# Fri3D_2026_Peripherals.net
KiCad netlist of a schematic drawn in Altium Designer
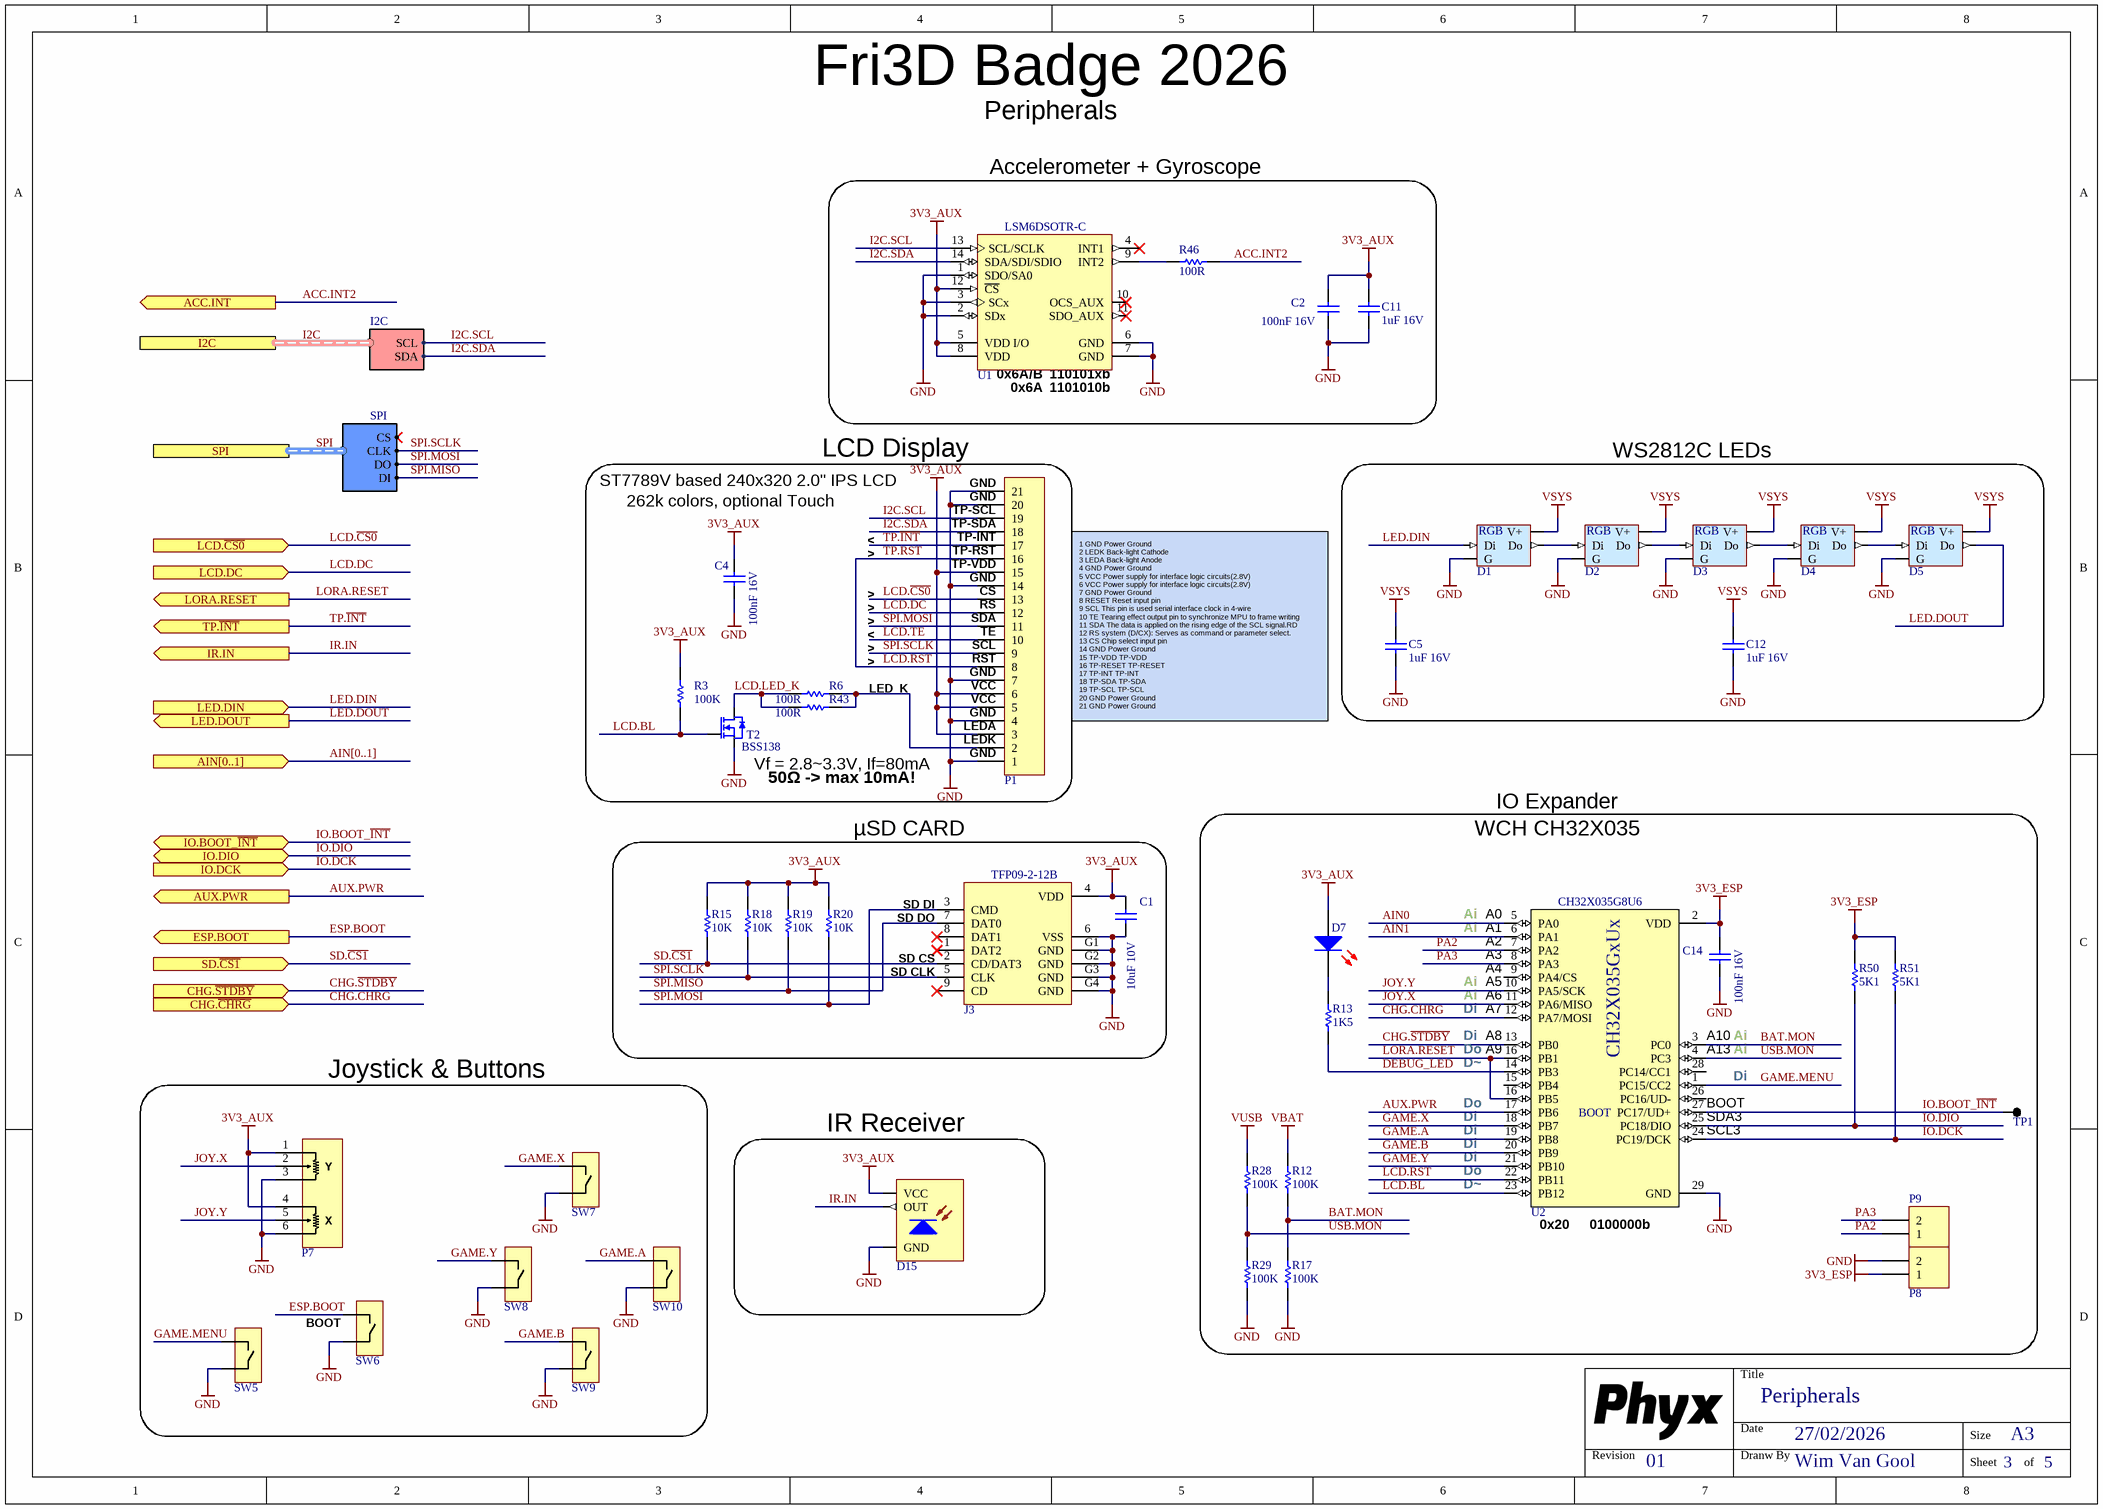
[diagram p0: Fri3D_2026_Peripherals.SchDoc]

(export (version "E")
  (design (tool "Eeschema 10.0.6"))
  (components
    (comp (ref "C1")
      (value "10uF 10V")
      (footprint "C0805_N")
      (description "Capacitor Ceramic")
      (libsource (lib "Phyx_Components") (part "CAP_CERAMIC"))
    )
    (comp (ref "C2")
      (value "100nF 16V")
      (footprint "C0603_N")
      (description "Capacitor Ceramic")
      (libsource (lib "Phyx_Components") (part "CAP_CERAMIC"))
    )
    (comp (ref "C4")
      (value "100nF 16V")
      (footprint "C0603_N")
      (description "Capacitor Ceramic")
      (libsource (lib "Phyx_Components") (part "CAP_CERAMIC"))
    )
    (comp (ref "C5")
      (value "1uF 16V")
      (footprint "C0603_N")
      (description "Capacitor Ceramic")
      (libsource (lib "Phyx_Components") (part "CAP_CERAMIC"))
    )
    (comp (ref "C11")
      (value "1uF 16V")
      (footprint "C0603_N")
      (description "Capacitor Ceramic")
      (libsource (lib "Phyx_Components") (part "CAP_CERAMIC"))
    )
    (comp (ref "C12")
      (value "1uF 16V")
      (footprint "C0603_N")
      (description "Capacitor Ceramic")
      (libsource (lib "Phyx_Components") (part "CAP_CERAMIC"))
    )
    (comp (ref "C14")
      (value "100nF 16V")
      (footprint "C0603_N")
      (description "Capacitor Ceramic")
      (libsource (lib "Phyx_Components") (part "CAP_CERAMIC"))
    )
    (comp (ref "D1")
      (value "WS2812 based digital RGB LED 5050 White package reduced current")
      (footprint "LED_5050_WS2812B_WHITE")
      (description "=Description")
      (libsource (lib "Phyx_Components") (part "LED_RGB_WS2812B_5050"))
    )
    (comp (ref "D2")
      (value "WS2812 based digital RGB LED 5050 White package reduced current")
      (footprint "LED_5050_WS2812B_WHITE")
      (description "=Description")
      (libsource (lib "Phyx_Components") (part "LED_RGB_WS2812B_5050"))
    )
    (comp (ref "D3")
      (value "WS2812 based digital RGB LED 5050 White package reduced current")
      (footprint "LED_5050_WS2812B_WHITE")
      (description "=Description")
      (libsource (lib "Phyx_Components") (part "LED_RGB_WS2812B_5050"))
    )
    (comp (ref "D4")
      (value "WS2812 based digital RGB LED 5050 White package reduced current")
      (footprint "LED_5050_WS2812B_WHITE")
      (description "=Description")
      (libsource (lib "Phyx_Components") (part "LED_RGB_WS2812B_5050"))
    )
    (comp (ref "D5")
      (value "WS2812 based digital RGB LED 5050 White package reduced current")
      (footprint "LED_5050_WS2812B_WHITE")
      (description "=Description")
      (libsource (lib "Phyx_Components") (part "LED_RGB_WS2812B_5050"))
    )
    (comp (ref "D7")
      (value "Default 0805 Red LED")
      (footprint "LED_0805_RD")
      (description "=Description")
      (libsource (lib "Phyx_Components") (part "LED_RED"))
    )
    (comp (ref "D15")
      (value "ZIRM-5042B-42-Z2 Infrared Receiver 38 kHz 45° 2.7-5.5V 940nm")
      (footprint "CHAU_ZIRM-5042B-42-Z2")
      (description "=Description")
      (libsource (lib "Phyx_Components") (part "PHO_IR_TSOP381x"))
    )
    (comp (ref "J3")
      (value "Micro SD PiPo Push-Push")
      (footprint "TFP09-2-12B")
      (description "=Description")
      (fields (field (name "SUPPLIER PART NUMBER 1") "TFP09-2-12B"))
      (libsource (lib "Phyx_Components") (part "TFP09-2-12B"))
    )
    (comp (ref "P1")
      (value "FH35C-21S-0.3SHW Top and Bottom Contacts 0.3mm 21pin")
      (footprint "HRS_FH35C-21S-0.3SHW")
      (libsource (lib "Phyx_Components") (part "Header 21"))
    )
    (comp (ref "P7")
      (value "PSP Mini Joystick")
      (footprint "PSP_Mini_Joystick")
      (libsource (lib "Phyx_Components") (part "PSP_Mini_Joystick"))
    )
    (comp (ref "P8")
      (value "Header 2")
      (footprint "HDR1X2")
      (libsource (lib "Phyx_Components") (part "Header 2"))
    )
    (comp (ref "P9")
      (value "Header 2")
      (footprint "HDR1X2")
      (libsource (lib "Phyx_Components") (part "Header 2"))
    )
    (comp (ref "R3")
      (value "100K")
      (footprint "R0603_N")
      (libsource (lib "Phyx_Components") (part "RESISTOR"))
    )
    (comp (ref "R6")
      (value "100R")
      (footprint "R0603_N")
      (libsource (lib "Phyx_Components") (part "RESISTOR"))
    )
    (comp (ref "R12")
      (value "100K")
      (footprint "R0603_N")
      (libsource (lib "Phyx_Components") (part "RESISTOR"))
    )
    (comp (ref "R13")
      (value "1K5")
      (footprint "R0603_N")
      (libsource (lib "Phyx_Components") (part "RESISTOR"))
    )
    (comp (ref "R15")
      (value "10K")
      (footprint "R0603_N")
      (libsource (lib "Phyx_Components") (part "RESISTOR"))
    )
    (comp (ref "R17")
      (value "100K")
      (footprint "R0603_N")
      (libsource (lib "Phyx_Components") (part "RESISTOR"))
    )
    (comp (ref "R18")
      (value "10K")
      (footprint "R0603_N")
      (libsource (lib "Phyx_Components") (part "RESISTOR"))
    )
    (comp (ref "R19")
      (value "10K")
      (footprint "R0603_N")
      (libsource (lib "Phyx_Components") (part "RESISTOR"))
    )
    (comp (ref "R20")
      (value "10K")
      (footprint "R0603_N")
      (libsource (lib "Phyx_Components") (part "RESISTOR"))
    )
    (comp (ref "R28")
      (value "100K")
      (footprint "R0603_N")
      (libsource (lib "Phyx_Components") (part "RESISTOR"))
    )
    (comp (ref "R29")
      (value "100K")
      (footprint "R0603_N")
      (libsource (lib "Phyx_Components") (part "RESISTOR"))
    )
    (comp (ref "R43")
      (value "100R")
      (footprint "R0603_N")
      (libsource (lib "Phyx_Components") (part "RESISTOR"))
    )
    (comp (ref "R46")
      (value "100R")
      (footprint "R0603_N")
      (libsource (lib "Phyx_Components") (part "RESISTOR"))
    )
    (comp (ref "R50")
      (value "5K1")
      (footprint "R0603_N")
      (libsource (lib "Phyx_Components") (part "RESISTOR"))
    )
    (comp (ref "R51")
      (value "5K1")
      (footprint "R0603_N")
      (libsource (lib "Phyx_Components") (part "RESISTOR"))
    )
    (comp (ref "SW5")
      (value "SKPMAME010 6x6 TACTG Switch")
      (footprint "ALPS_SKPMAME010")
      (libsource (lib "Phyx_Components") (part "SW_TACT"))
    )
    (comp (ref "SW6")
      (value "SKPMAME010 6x6 TACTG Switch")
      (footprint "ALPS_SKPMAME010")
      (libsource (lib "Phyx_Components") (part "SW_TACT"))
    )
    (comp (ref "SW7")
      (value "SKPMAME010 6x6 TACTG Switch")
      (footprint "ALPS_SKPMAME010")
      (libsource (lib "Phyx_Components") (part "SW_TACT"))
    )
    (comp (ref "SW8")
      (value "SKPMAME010 6x6 TACTG Switch")
      (footprint "ALPS_SKPMAME010")
      (libsource (lib "Phyx_Components") (part "SW_TACT"))
    )
    (comp (ref "SW9")
      (value "SKPMAME010 6x6 TACTG Switch")
      (footprint "ALPS_SKPMAME010")
      (libsource (lib "Phyx_Components") (part "SW_TACT"))
    )
    (comp (ref "SW10")
      (value "SKPMAME010 6x6 TACTG Switch")
      (footprint "ALPS_SKPMAME010")
      (libsource (lib "Phyx_Components") (part "SW_TACT"))
    )
    (comp (ref "T2")
      (value "BSS138")
      (footprint "SOT23-3")
      (fields (field (name "Comment") "0.2A N-Ch MOSFET Vgs 3.2"))
      (libsource (lib "Phyx_Components") (part "N_MOSFET_GSD"))
    )
    (comp (ref "TP1")
      (value "TEST_PAD")
      (footprint "TP_1.5mm_0.9mm")
      (libsource (lib "Phyx_Components") (part "TEST_PAD"))
    )
    (comp (ref "U1")
      (value "LSM6DSOTR-C")
      (footprint "STM_LGA14_2.5x3")
      (description "=Description")
      (fields (field (name "Comment") "Acceleration ±2, ±4, ±8, ±16g Gyro ±125, ±250, ±500, ±1000, ±2000dps"))
      (libsource (lib "Phyx_Components") (part "STM_LSM6DSO"))
    )
    (comp (ref "U2")
      (value "CH32X035G8U6")
      (footprint "QFN_28_4.0x4.0_P0.4")
      (fields
        (field (name "Comment") "WCH CH32X035G8U6 QFN28 RISC-V 32-bit MCU, 62KB Flash, 10KB RAM, USB PD")
      )
      (libsource (lib "Phyx_Components") (part "WCH_CH32X035GxUx"))
    )
  )
  (nets
    (net (code "3") (name "/ACC.INT2") (class "Default")
      (node (ref "R46") (pin "2") (pinfunction "2_2") (pintype "passive"))
    )
    (net (code "4") (name "/AIN0") (class "Default")
      (node (ref "U2") (pin "5") (pinfunction "PA0_5") (pintype "bidirectional"))
    )
    (net (code "5") (name "/AIN1") (class "Default")
      (node (ref "U2") (pin "6") (pinfunction "PA1_6") (pintype "bidirectional"))
    )
    (net (code "7") (name "/AUX.PWR") (class "Default")
      (node (ref "U2") (pin "17") (pinfunction "PB6_17") (pintype "bidirectional"))
    )
    (net (code "8") (name "/BAT.MON") (class "Default")
      (node (ref "R12") (pin "2") (pinfunction "2_2") (pintype "passive"))
      (node (ref "R17") (pin "1") (pinfunction "1_1") (pintype "passive"))
      (node (ref "U2") (pin "3") (pinfunction "PC0_3") (pintype "bidirectional"))
    )
    (net (code "9") (name "/CHG.~{CHRG}") (class "Default")
      (node (ref "U2") (pin "12") (pinfunction "PA7/MOSI_12") (pintype "bidirectional"))
    )
    (net (code "10") (name "/CHG.~{STDBY}") (class "Default")
      (node (ref "U2") (pin "13") (pinfunction "PB0_13") (pintype "bidirectional"))
    )
    (net (code "11") (name "/DEBUG_LED") (class "Default")
      (node (ref "R13") (pin "2") (pinfunction "2_2") (pintype "passive"))
      (node (ref "U2") (pin "14") (pinfunction "PB3_14") (pintype "bidirectional"))
    )
    (net (code "12") (name "/ESP.BOOT") (class "Default")
      (node (ref "SW6") (pin "1") (pinfunction "1_1") (pintype "passive"))
    )
    (net (code "13") (name "/GAME.A") (class "Default")
      (node (ref "SW10") (pin "1") (pinfunction "1_1") (pintype "passive"))
      (node (ref "U2") (pin "19") (pinfunction "PB8_19") (pintype "bidirectional"))
    )
    (net (code "14") (name "/GAME.B") (class "Default")
      (node (ref "SW9") (pin "1") (pinfunction "1_1") (pintype "passive"))
      (node (ref "U2") (pin "20") (pinfunction "PB9_20") (pintype "bidirectional"))
    )
    (net (code "15") (name "/GAME.MENU") (class "Default")
      (node (ref "SW5") (pin "1") (pinfunction "1_1") (pintype "passive"))
      (node (ref "U2") (pin "1") (pinfunction "PC15/CC2_1") (pintype "bidirectional"))
    )
    (net (code "16") (name "/GAME.X") (class "Default")
      (node (ref "SW7") (pin "1") (pinfunction "1_1") (pintype "passive"))
      (node (ref "U2") (pin "18") (pinfunction "PB7_18") (pintype "bidirectional"))
    )
    (net (code "17") (name "/GAME.Y") (class "Default")
      (node (ref "SW8") (pin "1") (pinfunction "1_1") (pintype "passive"))
      (node (ref "U2") (pin "21") (pinfunction "PB10_21") (pintype "bidirectional"))
    )
    (net (code "18") (name "/I2C.SCL") (class "Default")
      (node (ref "P1") (pin "19") (pinfunction "19_19") (pintype "passive"))
      (node (ref "U1") (pin "13") (pinfunction "SCL/SCLK_13") (pintype "input"))
    )
    (net (code "19") (name "/I2C.SDA") (class "Default")
      (node (ref "P1") (pin "18") (pinfunction "18_18") (pintype "passive"))
      (node (ref "U1") (pin "14") (pinfunction "SDA/SDI/SDIO_14") (pintype "bidirectional"))
    )
    (net (code "21") (name "/IO.BOOT_~{INT}") (class "Default")
      (node (ref "TP1") (pin "1") (pinfunction "1_1") (pintype "passive"))
      (node (ref "U2") (pin "27") (pinfunction "PC17/UD+_27") (pintype "bidirectional"))
    )
    (net (code "22") (name "/IO.DCK") (class "Default")
      (node (ref "R51") (pin "2") (pinfunction "2_2") (pintype "passive"))
      (node (ref "U2") (pin "24") (pinfunction "PC19/DCK_24") (pintype "bidirectional"))
    )
    (net (code "23") (name "/IO.DIO") (class "Default")
      (node (ref "R50") (pin "2") (pinfunction "2_2") (pintype "passive"))
      (node (ref "U2") (pin "25") (pinfunction "PC18/DIO_25") (pintype "bidirectional"))
    )
    (net (code "24") (name "/IR.IN") (class "Default")
      (node (ref "D15") (pin "1") (pinfunction "OUT_1") (pintype "output"))
    )
    (net (code "25") (name "/JOY.X") (class "Default")
      (node (ref "P7") (pin "2") (pinfunction "2_2") (pintype "passive"))
      (node (ref "U2") (pin "11") (pinfunction "PA6/MISO_11") (pintype "bidirectional"))
    )
    (net (code "26") (name "/JOY.Y") (class "Default")
      (node (ref "P7") (pin "5") (pinfunction "5_5") (pintype "passive"))
      (node (ref "U2") (pin "10") (pinfunction "PA5/SCK_10") (pintype "bidirectional"))
    )
    (net (code "27") (name "/LCD.BL") (class "Default")
      (node (ref "R3") (pin "2") (pinfunction "2_2") (pintype "passive"))
      (node (ref "T2") (pin "1") (pinfunction "G_1") (pintype "passive"))
      (node (ref "U2") (pin "23") (pinfunction "PB12_23") (pintype "bidirectional"))
    )
    (net (code "28") (name "/LCD.DC") (class "Default")
      (node (ref "P1") (pin "12") (pinfunction "12_12") (pintype "passive"))
    )
    (net (code "29") (name "/LCD.LED_K") (class "Default")
      (node (ref "R43") (pin "2") (pinfunction "2_2") (pintype "passive"))
      (node (ref "R6") (pin "2") (pinfunction "2_2") (pintype "passive"))
      (node (ref "T2") (pin "3") (pinfunction "D_3") (pintype "passive"))
    )
    (net (code "30") (name "/LCD.TE") (class "Default")
      (node (ref "P1") (pin "10") (pinfunction "10_10") (pintype "passive"))
    )
    (net (code "31") (name "/LCD.~{CS0}") (class "Default")
      (node (ref "P1") (pin "13") (pinfunction "13_13") (pintype "passive"))
    )
    (net (code "32") (name "/LCD.~{RST}") (class "Default")
      (node (ref "P1") (pin "16") (pinfunction "16_16") (pintype "passive"))
      (node (ref "P1") (pin "8") (pinfunction "8_8") (pintype "passive"))
      (node (ref "U2") (pin "22") (pinfunction "PB11_22") (pintype "bidirectional"))
    )
    (net (code "33") (name "/LED.DIN") (class "Default")
      (node (ref "D1") (pin "4") (pinfunction "Di_4") (pintype "input"))
    )
    (net (code "34") (name "/LED.DOUT") (class "Default")
      (node (ref "D5") (pin "2") (pinfunction "Do_2") (pintype "output"))
    )
    (net (code "35") (name "/LORA.RESET") (class "Default")
      (node (ref "U2") (pin "16") (pinfunction "PB1_16") (pintype "bidirectional"))
    )
    (net (code "36") (name "/PA2") (class "Default")
      (node (ref "P9") (pin "1") (pinfunction "1_1") (pintype "passive"))
      (node (ref "U2") (pin "7") (pinfunction "PA2_7") (pintype "bidirectional"))
    )
    (net (code "37") (name "/PA3") (class "Default")
      (node (ref "P9") (pin "2") (pinfunction "2_2") (pintype "passive"))
      (node (ref "U2") (pin "8") (pinfunction "PA3_8") (pintype "bidirectional"))
    )
    (net (code "38") (name "/SD.~{CS1}") (class "Default")
      (node (ref "J3") (pin "2") (pinfunction "CD/DAT3_2") (pintype "passive"))
      (node (ref "R15") (pin "2") (pinfunction "2_2") (pintype "passive"))
    )
    (net (code "39") (name "/SPI.MISO") (class "Default")
      (node (ref "J3") (pin "7") (pinfunction "DAT0_7") (pintype "passive"))
      (node (ref "R19") (pin "2") (pinfunction "2_2") (pintype "passive"))
    )
    (net (code "40") (name "/SPI.MOSI") (class "Default")
      (node (ref "J3") (pin "3") (pinfunction "CMD_3") (pintype "passive"))
      (node (ref "P1") (pin "11") (pinfunction "11_11") (pintype "passive"))
      (node (ref "R20") (pin "2") (pinfunction "2_2") (pintype "passive"))
    )
    (net (code "41") (name "/SPI.SCLK") (class "Default")
      (node (ref "J3") (pin "5") (pinfunction "CLK_5") (pintype "passive"))
      (node (ref "P1") (pin "9") (pinfunction "9_9") (pintype "passive"))
      (node (ref "R18") (pin "2") (pinfunction "2_2") (pintype "passive"))
    )
    (net (code "43") (name "/TP.~{INT}") (class "Default")
      (node (ref "P1") (pin "17") (pinfunction "17_17") (pintype "passive"))
    )
    (net (code "44") (name "/USB.MON") (class "Default")
      (node (ref "R28") (pin "2") (pinfunction "2_2") (pintype "passive"))
      (node (ref "R29") (pin "1") (pinfunction "1_1") (pintype "passive"))
      (node (ref "U2") (pin "4") (pinfunction "PC3_4") (pintype "bidirectional"))
    )
    (net (code "45") (name "3V3_AUX") (class "Default")
      (node (ref "C1") (pin "1") (pinfunction "1_1") (pintype "passive"))
      (node (ref "C11") (pin "1") (pinfunction "1_1") (pintype "passive"))
      (node (ref "C2") (pin "1") (pinfunction "1_1") (pintype "passive"))
      (node (ref "C4") (pin "1") (pinfunction "1_1") (pintype "passive"))
      (node (ref "D15") (pin "3") (pinfunction "VCC_3") (pintype "power_in"))
      (node (ref "D7") (pin "1") (pinfunction "A_1") (pintype "passive"))
      (node (ref "J3") (pin "4") (pinfunction "VDD_4") (pintype "power_in"))
      (node (ref "P1") (pin "15") (pinfunction "15_15") (pintype "passive"))
      (node (ref "P1") (pin "3") (pinfunction "3_3") (pintype "passive"))
      (node (ref "P1") (pin "5") (pinfunction "5_5") (pintype "passive"))
      (node (ref "P1") (pin "6") (pinfunction "6_6") (pintype "passive"))
      (node (ref "P7") (pin "1") (pinfunction "1_1") (pintype "passive"))
      (node (ref "P7") (pin "4") (pinfunction "4_4") (pintype "passive"))
      (node (ref "R15") (pin "1") (pinfunction "1_1") (pintype "passive"))
      (node (ref "R18") (pin "1") (pinfunction "1_1") (pintype "passive"))
      (node (ref "R19") (pin "1") (pinfunction "1_1") (pintype "passive"))
      (node (ref "R20") (pin "1") (pinfunction "1_1") (pintype "passive"))
      (node (ref "R3") (pin "1") (pinfunction "1_1") (pintype "passive"))
      (node (ref "U1") (pin "12") (pinfunction "~{CS}_12") (pintype "input"))
      (node (ref "U1") (pin "5") (pinfunction "VDD_I/O_5") (pintype "power_in"))
      (node (ref "U1") (pin "8") (pinfunction "VDD_8") (pintype "power_in"))
    )
    (net (code "46") (name "3V3_ESP") (class "Default")
      (node (ref "C14") (pin "1") (pinfunction "1_1") (pintype "passive"))
      (node (ref "P8") (pin "1") (pinfunction "1_1") (pintype "passive"))
      (node (ref "R50") (pin "1") (pinfunction "1_1") (pintype "passive"))
      (node (ref "R51") (pin "1") (pinfunction "1_1") (pintype "passive"))
      (node (ref "U2") (pin "2") (pinfunction "VDD_2") (pintype "power_in"))
    )
    (net (code "47") (name "GND") (class "Default")
      (node (ref "C1") (pin "2") (pinfunction "2_2") (pintype "passive"))
      (node (ref "C11") (pin "2") (pinfunction "2_2") (pintype "passive"))
      (node (ref "C12") (pin "2") (pinfunction "2_2") (pintype "passive"))
      (node (ref "C14") (pin "2") (pinfunction "2_2") (pintype "passive"))
      (node (ref "C2") (pin "2") (pinfunction "2_2") (pintype "passive"))
      (node (ref "C4") (pin "2") (pinfunction "2_2") (pintype "passive"))
      (node (ref "C5") (pin "2") (pinfunction "2_2") (pintype "passive"))
      (node (ref "D1") (pin "3") (pinfunction "G_3") (pintype "power_in"))
      (node (ref "D15") (pin "2") (pinfunction "GND_2") (pintype "power_in"))
      (node (ref "D2") (pin "3") (pinfunction "G_3") (pintype "power_in"))
      (node (ref "D3") (pin "3") (pinfunction "G_3") (pintype "power_in"))
      (node (ref "D4") (pin "3") (pinfunction "G_3") (pintype "power_in"))
      (node (ref "D5") (pin "3") (pinfunction "G_3") (pintype "power_in"))
      (node (ref "J3") (pin "6") (pinfunction "VSS_6") (pintype "power_in"))
      (node (ref "J3") (pin "G1") (pinfunction "GND_G1") (pintype "power_in"))
      (node (ref "J3") (pin "G2") (pinfunction "GND_G2") (pintype "power_in"))
      (node (ref "J3") (pin "G3") (pinfunction "GND_G3") (pintype "power_in"))
      (node (ref "J3") (pin "G4") (pinfunction "GND_G4") (pintype "power_in"))
      (node (ref "P1") (pin "1") (pinfunction "1_1") (pintype "passive"))
      (node (ref "P1") (pin "14") (pinfunction "14_14") (pintype "passive"))
      (node (ref "P1") (pin "20") (pinfunction "20_20") (pintype "passive"))
      (node (ref "P1") (pin "21") (pinfunction "21_21") (pintype "passive"))
      (node (ref "P1") (pin "4") (pinfunction "4_4") (pintype "passive"))
      (node (ref "P1") (pin "7") (pinfunction "7_7") (pintype "passive"))
      (node (ref "P7") (pin "3") (pinfunction "3_3") (pintype "passive"))
      (node (ref "P7") (pin "6") (pinfunction "6_6") (pintype "passive"))
      (node (ref "P8") (pin "2") (pinfunction "2_2") (pintype "passive"))
      (node (ref "R17") (pin "2") (pinfunction "2_2") (pintype "passive"))
      (node (ref "R29") (pin "2") (pinfunction "2_2") (pintype "passive"))
      (node (ref "SW10") (pin "2") (pinfunction "2_2") (pintype "passive"))
      (node (ref "SW5") (pin "2") (pinfunction "2_2") (pintype "passive"))
      (node (ref "SW6") (pin "2") (pinfunction "2_2") (pintype "passive"))
      (node (ref "SW7") (pin "2") (pinfunction "2_2") (pintype "passive"))
      (node (ref "SW8") (pin "2") (pinfunction "2_2") (pintype "passive"))
      (node (ref "SW9") (pin "2") (pinfunction "2_2") (pintype "passive"))
      (node (ref "T2") (pin "2") (pinfunction "S_2") (pintype "passive"))
      (node (ref "U1") (pin "1") (pinfunction "SDO/SA0_1") (pintype "bidirectional"))
      (node (ref "U1") (pin "2") (pinfunction "SDx_2") (pintype "bidirectional"))
      (node (ref "U1") (pin "3") (pinfunction "SCx_3") (pintype "output"))
      (node (ref "U1") (pin "6") (pinfunction "GND_6") (pintype "power_in"))
      (node (ref "U1") (pin "7") (pinfunction "GND_7") (pintype "power_in"))
      (node (ref "U2") (pin "29") (pinfunction "GND_29") (pintype "power_in"))
    )
    (net (code "48") (name "Net-(D1-Do)") (class "Default")
      (node (ref "D1") (pin "2") (pinfunction "Do_2") (pintype "output"))
      (node (ref "D2") (pin "4") (pinfunction "Di_4") (pintype "input"))
    )
    (net (code "49") (name "Net-(D2-Do)") (class "Default")
      (node (ref "D2") (pin "2") (pinfunction "Do_2") (pintype "output"))
      (node (ref "D3") (pin "4") (pinfunction "Di_4") (pintype "input"))
    )
    (net (code "50") (name "Net-(D3-Do)") (class "Default")
      (node (ref "D3") (pin "2") (pinfunction "Do_2") (pintype "output"))
      (node (ref "D4") (pin "4") (pinfunction "Di_4") (pintype "input"))
    )
    (net (code "51") (name "Net-(D4-Do)") (class "Default")
      (node (ref "D4") (pin "2") (pinfunction "Do_2") (pintype "output"))
      (node (ref "D5") (pin "4") (pinfunction "Di_4") (pintype "input"))
    )
    (net (code "52") (name "Net-(D7-K)") (class "Default")
      (node (ref "D7") (pin "2") (pinfunction "K_2") (pintype "passive"))
      (node (ref "R13") (pin "1") (pinfunction "1_1") (pintype "passive"))
    )
    (net (code "53") (name "Net-(P1-Pad2)") (class "Default")
      (node (ref "P1") (pin "2") (pinfunction "2_2") (pintype "passive"))
      (node (ref "R43") (pin "1") (pinfunction "1_1") (pintype "passive"))
      (node (ref "R6") (pin "1") (pinfunction "1_1") (pintype "passive"))
    )
    (net (code "54") (name "Net-(U1-INT2)") (class "Default")
      (node (ref "R46") (pin "1") (pinfunction "1_1") (pintype "passive"))
      (node (ref "U1") (pin "9") (pinfunction "INT2_9") (pintype "output"))
    )
    (net (code "55") (name "VBAT") (class "Default")
      (node (ref "R12") (pin "1") (pinfunction "1_1") (pintype "passive"))
    )
    (net (code "56") (name "VSYS") (class "Default")
      (node (ref "C12") (pin "1") (pinfunction "1_1") (pintype "passive"))
      (node (ref "C5") (pin "1") (pinfunction "1_1") (pintype "passive"))
      (node (ref "D1") (pin "1") (pinfunction "V+_1") (pintype "power_in"))
      (node (ref "D2") (pin "1") (pinfunction "V+_1") (pintype "power_in"))
      (node (ref "D3") (pin "1") (pinfunction "V+_1") (pintype "power_in"))
      (node (ref "D4") (pin "1") (pinfunction "V+_1") (pintype "power_in"))
      (node (ref "D5") (pin "1") (pinfunction "V+_1") (pintype "power_in"))
    )
    (net (code "57") (name "VUSB") (class "Default")
      (node (ref "R28") (pin "1") (pinfunction "1_1") (pintype "passive"))
    )
    (net (code "58") (name "unconnected-(J3-CD-Pad9)") (class "Default")
      (node (ref "J3") (pin "9") (pinfunction "CD_9") (pintype "passive+no_connect"))
    )
    (net (code "59") (name "unconnected-(J3-DAT1-Pad8)") (class "Default")
      (node (ref "J3") (pin "8") (pinfunction "DAT1_8") (pintype "passive+no_connect"))
    )
    (net (code "60") (name "unconnected-(J3-DAT2-Pad1)") (class "Default")
      (node (ref "J3") (pin "1") (pinfunction "DAT2_1") (pintype "passive+no_connect"))
    )
    (net (code "61") (name "unconnected-(U1-INT1-Pad4)") (class "Default")
      (node (ref "U1") (pin "4") (pinfunction "INT1_4") (pintype "output+no_connect"))
    )
    (net (code "62") (name "unconnected-(U1-OCS_AUX-Pad10)") (class "Default")
      (node (ref "U1") (pin "10") (pinfunction "OCS_AUX_10") (pintype "passive+no_connect"))
    )
    (net (code "63") (name "unconnected-(U1-SDO_AUX-Pad11)") (class "Default")
      (node (ref "U1") (pin "11") (pinfunction "SDO_AUX_11") (pintype "output+no_connect"))
    )
    (net (code "64") (name "unconnected-(U2-PA4{slash}CS-Pad9)") (class "Default")
      (node (ref "U2") (pin "9") (pinfunction "PA4/CS_9") (pintype "bidirectional"))
    )
    (net (code "65") (name "unconnected-(U2-PB4-Pad15)") (class "Default")
      (node (ref "U2") (pin "15") (pinfunction "PB4_15") (pintype "bidirectional"))
    )
    (net (code "66") (name "unconnected-(U2-PC14{slash}CC1-Pad28)") (class "Default")
      (node (ref "U2") (pin "28") (pinfunction "PC14/CC1_28") (pintype "bidirectional"))
    )
    (net (code "67") (name "unconnected-(U2-PC16{slash}UD--Pad26)") (class "Default")
      (node (ref "U2") (pin "26") (pinfunction "PC16/UD-_26") (pintype "bidirectional"))
    )
  )
)
